# PCB_1d.net
KiCad netlist of a schematic drawn in EAGLE
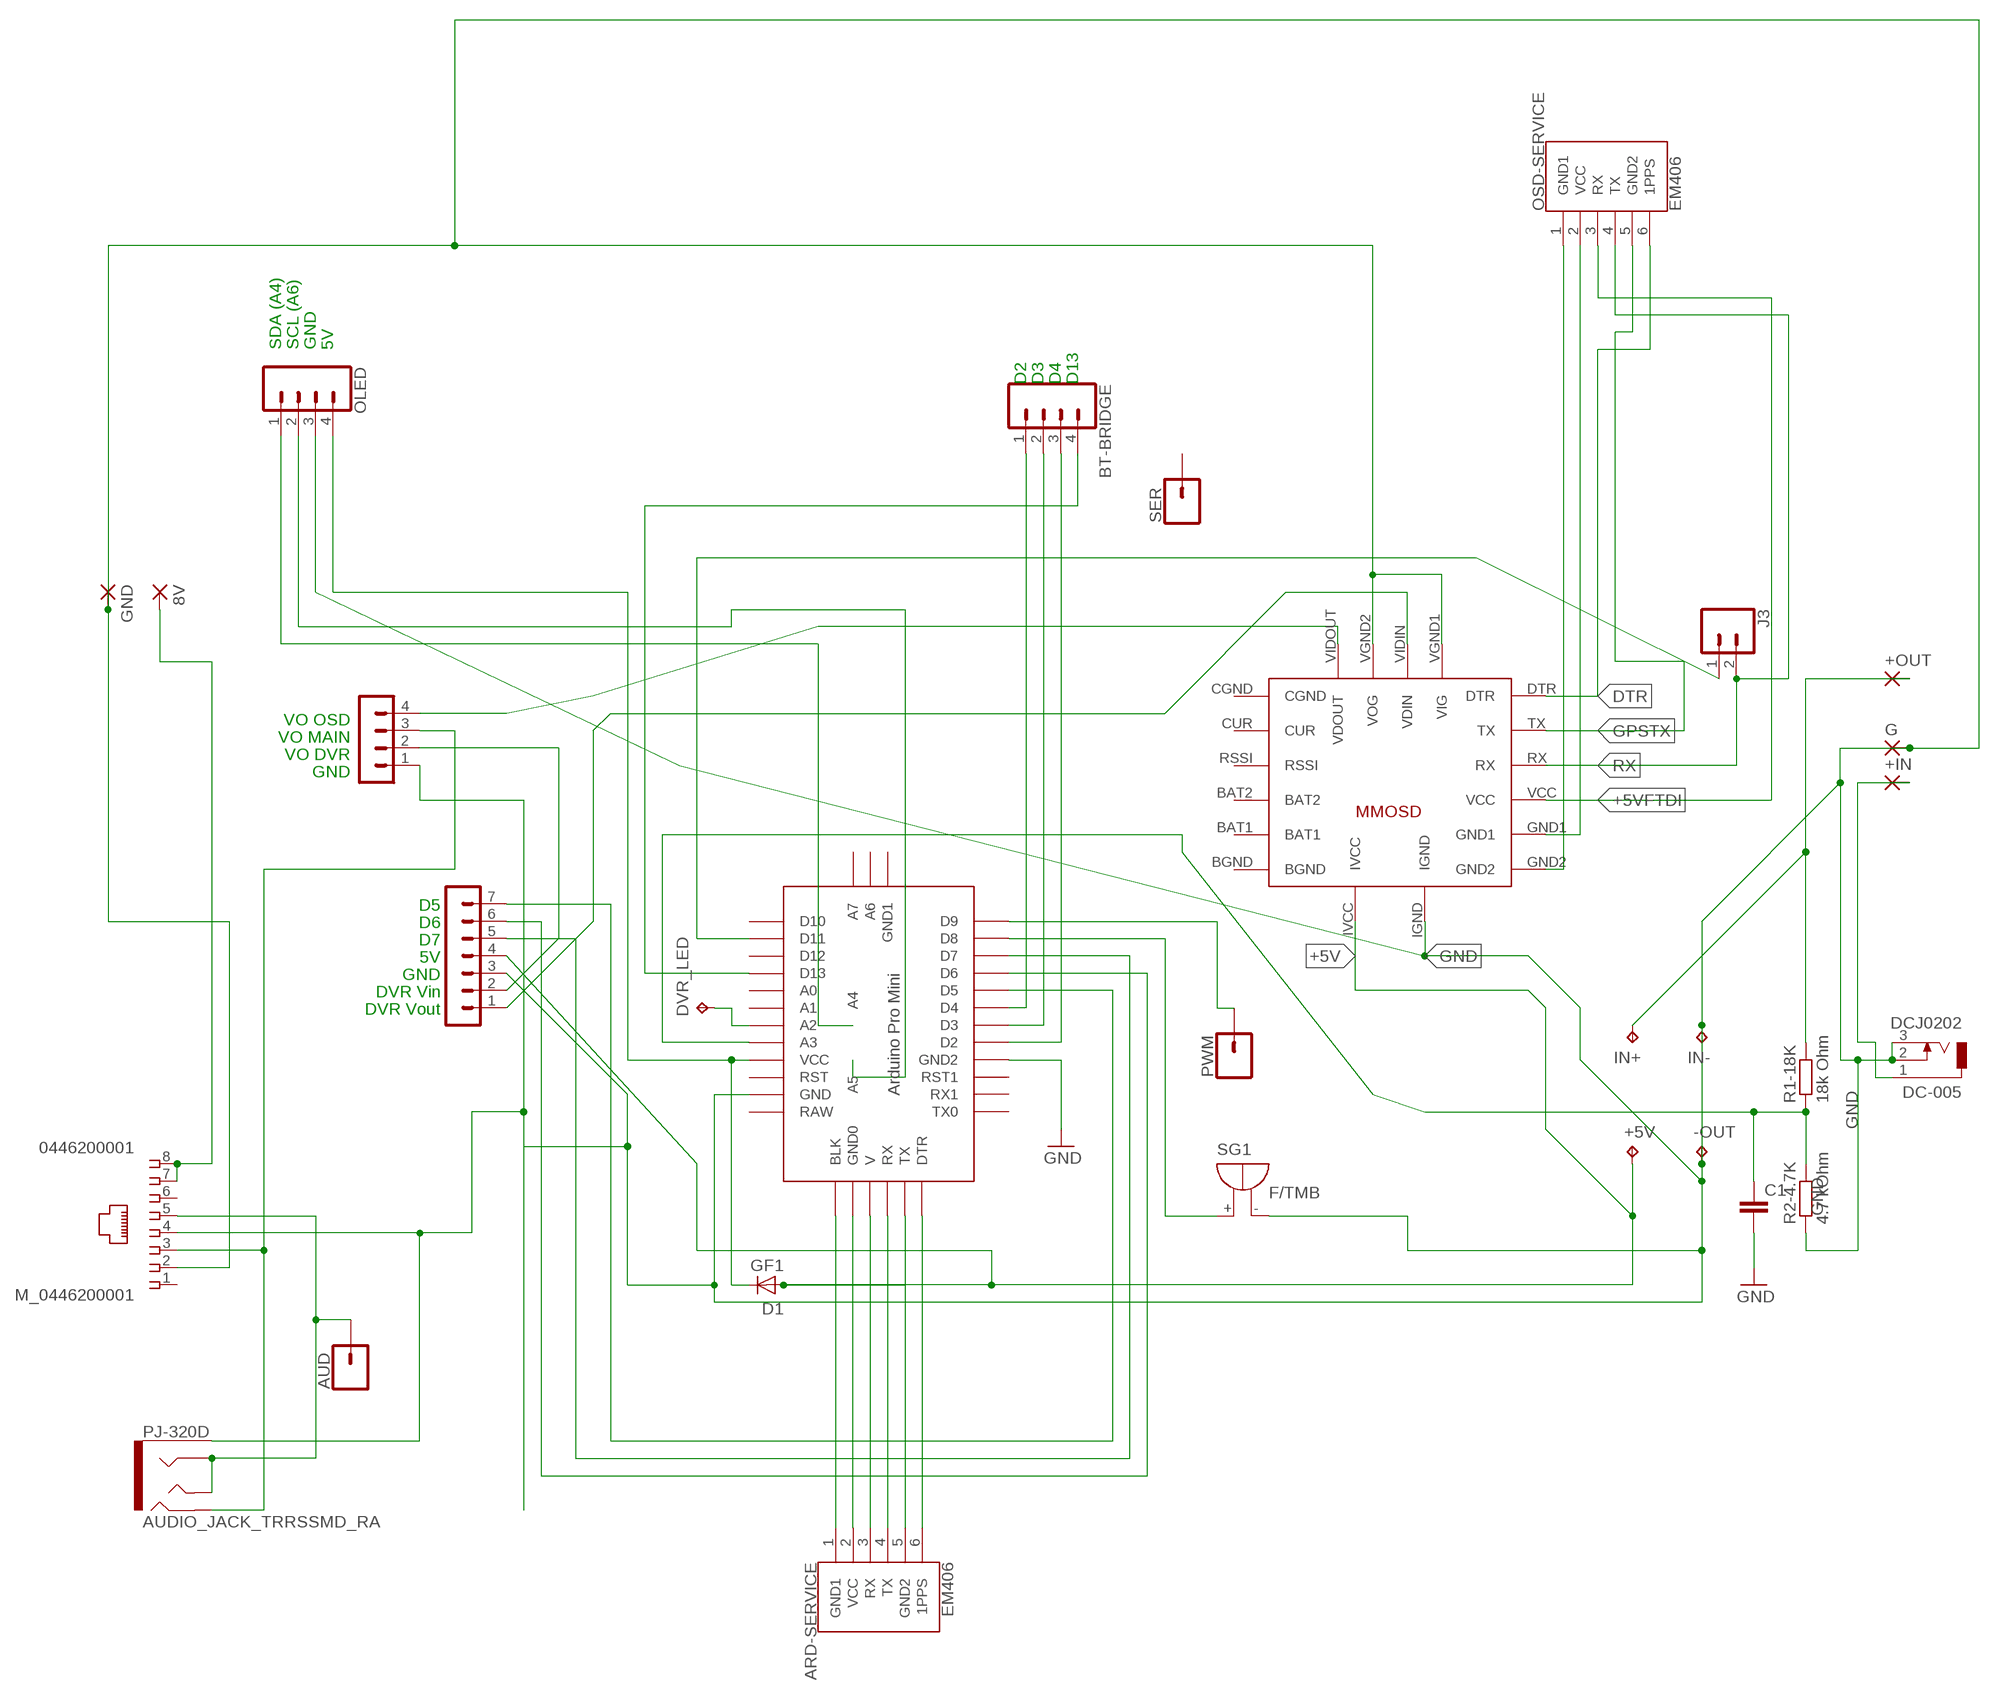
[diagram p0: schematic, sheet 1]

(export (version "E")
  (design (tool "Eeschema 10.0.6"))
  (components
    (comp (ref "+5V")
      (value "TPTP20SQ")
      (footprint "eagle-import:TP20SQ")
      (libsource (lib "eagle-import") (part "TPTP20SQ"))
    )
    (comp (ref "+IN")
      (value "2,54/1,1")
      (footprint "eagle-import:2,54_1,1")
      (libsource (lib "eagle-import") (part "2,54/1,1"))
    )
    (comp (ref "+OUT")
      (value "2,54/1,1")
      (footprint "eagle-import:2,54_1,1")
      (libsource (lib "eagle-import") (part "2,54/1,1"))
    )
    (comp (ref "-OUT")
      (value "TPTP20SQ")
      (footprint "eagle-import:TP20SQ")
      (libsource (lib "eagle-import") (part "TPTP20SQ"))
    )
    (comp (ref "8V")
      (value "2,54/1,1")
      (footprint "eagle-import:2,54_1,1")
      (libsource (lib "eagle-import") (part "2,54/1,1"))
    )
    (comp (ref "ARD-SERVICE")
      (value "EM406")
      (footprint "eagle-import:1X06-1MM")
      (libsource (lib "eagle-import") (part "EM406"))
    )
    (comp (ref "AUD")
      (value "CONN_01")
      (footprint "eagle-import:1X01")
      (libsource (lib "eagle-import") (part "CONN_01"))
    )
    (comp (ref "BT-BRIDGE")
      (value "CONN_04")
      (footprint "eagle-import:1X04")
      (libsource (lib "eagle-import") (part "CONN_04"))
    )
    (comp (ref "C1")
      (value "C-EUC1206K")
      (footprint "eagle-import:C1206K")
      (libsource (lib "eagle-import") (part "C-EUC1206K"))
    )
    (comp (ref "D1")
      (value "GF1")
      (footprint "eagle-import:SMA-DO214AC")
      (libsource (lib "eagle-import") (part "GF1"))
    )
    (comp (ref "DC-005")
      (value "DCJ0202")
      (footprint "eagle-import:DCJ0202")
      (libsource (lib "eagle-import") (part "DCJ0202"))
    )
    (comp (ref "DVR_LED")
      (value "TPTP20SQ")
      (footprint "eagle-import:TP20SQ")
      (libsource (lib "eagle-import") (part "TPTP20SQ"))
    )
    (comp (ref "G")
      (value "2,54/1,1")
      (footprint "eagle-import:2,54_1,1")
      (libsource (lib "eagle-import") (part "2,54/1,1"))
    )
    (comp (ref "GND")
      (value "2,54/1,1")
      (footprint "eagle-import:2,54_1,1")
      (libsource (lib "eagle-import") (part "2,54/1,1"))
    )
    (comp (ref "IN+")
      (value "TPTP20SQ")
      (footprint "eagle-import:TP20SQ")
      (libsource (lib "eagle-import") (part "TPTP20SQ"))
    )
    (comp (ref "IN-")
      (value "TPTP20SQ")
      (footprint "eagle-import:TP20SQ")
      (libsource (lib "eagle-import") (part "TPTP20SQ"))
    )
    (comp (ref "J3")
      (value "CONN_02")
      (footprint "eagle-import:1X02")
      (libsource (lib "eagle-import") (part "CONN_02"))
    )
    (comp (ref "MINIMOSD")
      (value "MICROMINIMOSDPWR")
      (footprint "eagle-import:MMOSDNVDVID")
      (libsource (lib "eagle-import") (part "MICROMINIMOSDPWR"))
    )
    (comp (ref "MODULE-IO")
      (value "MA07-1")
      (footprint "eagle-import:MA07-1")
      (libsource (lib "eagle-import") (part "MA07-1"))
    )
    (comp (ref "M_0446200001")
      (value "0446200001")
      (footprint "eagle-import:0446200001")
      (fields (field (name "MF") "MOLEX"))
      (libsource (lib "eagle-import") (part "0446200001"))
    )
    (comp (ref "OLED")
      (value "CONN_04")
      (footprint "eagle-import:1X04")
      (libsource (lib "eagle-import") (part "CONN_04"))
    )
    (comp (ref "OSD-SERVICE")
      (value "EM406")
      (footprint "eagle-import:1X06-1MM")
      (libsource (lib "eagle-import") (part "EM406"))
    )
    (comp (ref "PJ-320D")
      (value "AUDIO_JACK_TRRSSMD_RA")
      (footprint "eagle-import:AUDIO_JACK_3.5MM_TRRS_SMD_RA")
      (libsource (lib "eagle-import") (part "AUDIO_JACK_TRRSSMD_RA"))
    )
    (comp (ref "PWM")
      (value "CONN_01")
      (footprint "eagle-import:1X01")
      (libsource (lib "eagle-import") (part "CONN_01"))
    )
    (comp (ref "R1-18K")
      (value "18k Ohm")
      (footprint "eagle-import:M1206")
      (libsource (lib "eagle-import") (part "R-EU_M1206"))
    )
    (comp (ref "R2-4.7K")
      (value "4.7 kOhm")
      (footprint "eagle-import:M1206")
      (libsource (lib "eagle-import") (part "R-EU_M1206"))
    )
    (comp (ref "SER")
      (value "CONN_01")
      (footprint "eagle-import:1X01")
      (libsource (lib "eagle-import") (part "CONN_01"))
    )
    (comp (ref "SG1")
      (value "F/TMB")
      (footprint "eagle-import:F_TMB")
      (libsource (lib "eagle-import") (part "F/TMB"))
    )
    (comp (ref "U$1")
      (value "ABK-PRO-MINI")
      (footprint "eagle-import:ABK-PRO-MINI")
      (libsource (lib "eagle-import") (part "ABK-PRO-MINI"))
    )
    (comp (ref "V-IO")
      (value "MA04-1")
      (footprint "eagle-import:MA04-1")
      (libsource (lib "eagle-import") (part "MA04-1"))
    )
  )
  (nets
    (net (code "1") (name "+5V") (class "Default")
      (node (ref "+5V") (pin "TP") (pinfunction "TP_TP") (pintype "input"))
      (node (ref "D1") (pin "A") (pinfunction "A_A") (pintype "passive"))
      (node (ref "MINIMOSD") (pin "IVCC") (pinfunction "IVCC_IVCC") (pintype "power_in"))
      (node (ref "MODULE-IO") (pin "4") (pinfunction "4_4") (pintype "passive"))
    )
    (net (code "2") (name "+5VFTDI") (class "Default")
      (node (ref "MINIMOSD") (pin "VCC") (pinfunction "VCC_VCC") (pintype "power_in"))
      (node (ref "OSD-SERVICE") (pin "3") (pinfunction "RX_3") (pintype "bidirectional"))
    )
    (net (code "3") (name "/BAT1") (class "Default")
      (node (ref "MINIMOSD") (pin "BAT1") (pinfunction "BAT1_BAT1") (pintype "power_in"))
    )
    (net (code "4") (name "/BAT2") (class "Default")
      (node (ref "MINIMOSD") (pin "BAT2") (pinfunction "BAT2_BAT2") (pintype "power_in"))
    )
    (net (code "5") (name "/BGND") (class "Default")
      (node (ref "MINIMOSD") (pin "BGND") (pinfunction "BGND_BGND") (pintype "power_in"))
    )
    (net (code "6") (name "/CGND") (class "Default")
      (node (ref "MINIMOSD") (pin "CGND") (pinfunction "CGND_CGND") (pintype "power_in"))
    )
    (net (code "7") (name "DTR") (class "Default")
      (node (ref "MINIMOSD") (pin "DTR") (pinfunction "DTR_DTR") (pintype "bidirectional"))
      (node (ref "OSD-SERVICE") (pin "6") (pinfunction "1PPS_6") (pintype "bidirectional"))
    )
    (net (code "8") (name "GND") (class "Default")
      (node (ref "-OUT") (pin "TP") (pinfunction "TP_TP") (pintype "input"))
      (node (ref "C1") (pin "2") (pinfunction "2_2") (pintype "passive"))
      (node (ref "DC-005") (pin "2") (pinfunction "2_2") (pintype "passive"))
      (node (ref "DC-005") (pin "3") (pinfunction "3_3") (pintype "passive"))
      (node (ref "G") (pin "1") (pinfunction "P_1") (pintype "passive"))
      (node (ref "GND") (pin "1") (pinfunction "P_1") (pintype "passive"))
      (node (ref "IN-") (pin "TP") (pinfunction "TP_TP") (pintype "input"))
      (node (ref "MINIMOSD") (pin "IGND") (pinfunction "IGND_IGND") (pintype "power_in"))
      (node (ref "MINIMOSD") (pin "VGND1") (pinfunction "VIG_VGND1") (pintype "input"))
      (node (ref "MINIMOSD") (pin "VGND2") (pinfunction "VOG_VGND2") (pintype "output"))
      (node (ref "MODULE-IO") (pin "3") (pinfunction "3_3") (pintype "passive"))
      (node (ref "M_0446200001") (pin "2") (pinfunction "2_2") (pintype "passive"))
      (node (ref "M_0446200001") (pin "4") (pinfunction "4_4") (pintype "passive"))
      (node (ref "OLED") (pin "3") (pinfunction "3_3") (pintype "passive"))
      (node (ref "PJ-320D") (pin "EARTH") (pinfunction "EARTH_EARTH") (pintype "bidirectional"))
      (node (ref "R2-4.7K") (pin "1") (pinfunction "1_1") (pintype "passive"))
      (node (ref "SG1") (pin "-") (pinfunction "-_-") (pintype "passive"))
      (node (ref "U$1") (pin "GND") (pinfunction "GND_GND") (pintype "bidirectional"))
      (node (ref "U$1") (pin "GND1") (pinfunction "GND2_GND1") (pintype "bidirectional"))
      (node (ref "V-IO") (pin "1") (pinfunction "1_1") (pintype "passive"))
    )
    (net (code "9") (name "GPSTX") (class "Default")
      (node (ref "MINIMOSD") (pin "TX") (pinfunction "TX_TX") (pintype "output"))
      (node (ref "OSD-SERVICE") (pin "5") (pinfunction "GND2_5") (pintype "bidirectional"))
    )
    (net (code "10") (name "Net-(+IN-P)") (class "Default")
      (node (ref "+IN") (pin "1") (pinfunction "P_1") (pintype "passive"))
      (node (ref "DC-005") (pin "1") (pinfunction "1_1") (pintype "passive"))
    )
    (net (code "11") (name "Net-(+OUT-P)") (class "Default")
      (node (ref "+OUT") (pin "1") (pinfunction "P_1") (pintype "passive"))
      (node (ref "IN+") (pin "TP") (pinfunction "TP_TP") (pintype "input"))
      (node (ref "R1-18K") (pin "2") (pinfunction "2_2") (pintype "passive"))
    )
    (net (code "12") (name "Net-(8V-P)") (class "Default")
      (node (ref "8V") (pin "1") (pinfunction "P_1") (pintype "passive"))
      (node (ref "M_0446200001") (pin "7") (pinfunction "7_7") (pintype "passive"))
      (node (ref "M_0446200001") (pin "8") (pinfunction "8_8") (pintype "passive"))
    )
    (net (code "13") (name "Net-(ARD-SERVICE-1PPS)") (class "Default")
      (node (ref "ARD-SERVICE") (pin "6") (pinfunction "1PPS_6") (pintype "bidirectional"))
      (node (ref "U$1") (pin "DTR") (pinfunction "DTR_DTR") (pintype "bidirectional"))
    )
    (net (code "14") (name "Net-(ARD-SERVICE-GND1)") (class "Default")
      (node (ref "ARD-SERVICE") (pin "1") (pinfunction "GND1_1") (pintype "bidirectional"))
      (node (ref "U$1") (pin "BLK") (pinfunction "BLK_BLK") (pintype "bidirectional"))
    )
    (net (code "15") (name "Net-(ARD-SERVICE-GND2)") (class "Default")
      (node (ref "ARD-SERVICE") (pin "5") (pinfunction "GND2_5") (pintype "bidirectional"))
      (node (ref "U$1") (pin "TX01") (pinfunction "TX_TX01") (pintype "bidirectional"))
    )
    (net (code "16") (name "Net-(ARD-SERVICE-RX)") (class "Default")
      (node (ref "ARD-SERVICE") (pin "3") (pinfunction "RX_3") (pintype "bidirectional"))
      (node (ref "U$1") (pin "5V") (pinfunction "V_5V") (pintype "bidirectional"))
    )
    (net (code "17") (name "Net-(ARD-SERVICE-TX)") (class "Default")
      (node (ref "ARD-SERVICE") (pin "4") (pinfunction "TX_4") (pintype "bidirectional"))
      (node (ref "U$1") (pin "RX01") (pinfunction "RX_RX01") (pintype "bidirectional"))
    )
    (net (code "18") (name "Net-(ARD-SERVICE-VCC)") (class "Default")
      (node (ref "ARD-SERVICE") (pin "2") (pinfunction "VCC_2") (pintype "bidirectional"))
      (node (ref "U$1") (pin "G") (pinfunction "GND0_G") (pintype "bidirectional"))
    )
    (net (code "19") (name "Net-(AUD-Pad1)") (class "Default")
      (node (ref "AUD") (pin "1") (pinfunction "1_1") (pintype "passive"))
      (node (ref "M_0446200001") (pin "5") (pinfunction "5_5") (pintype "passive"))
      (node (ref "PJ-320D") (pin "RING1") (pinfunction "RING1_RING1") (pintype "bidirectional"))
      (node (ref "PJ-320D") (pin "TIP") (pinfunction "TIP_TIP") (pintype "bidirectional"))
    )
    (net (code "20") (name "Net-(BT-BRIDGE-Pad1)") (class "Default")
      (node (ref "BT-BRIDGE") (pin "1") (pinfunction "1_1") (pintype "passive"))
      (node (ref "U$1") (pin "D4") (pinfunction "D4_D4") (pintype "bidirectional"))
    )
    (net (code "21") (name "Net-(BT-BRIDGE-Pad2)") (class "Default")
      (node (ref "BT-BRIDGE") (pin "2") (pinfunction "2_2") (pintype "passive"))
      (node (ref "U$1") (pin "D3") (pinfunction "D3_D3") (pintype "bidirectional"))
    )
    (net (code "22") (name "Net-(BT-BRIDGE-Pad3)") (class "Default")
      (node (ref "BT-BRIDGE") (pin "3") (pinfunction "3_3") (pintype "passive"))
      (node (ref "U$1") (pin "D2") (pinfunction "D2_D2") (pintype "bidirectional"))
    )
    (net (code "23") (name "Net-(BT-BRIDGE-Pad4)") (class "Default")
      (node (ref "BT-BRIDGE") (pin "4") (pinfunction "4_4") (pintype "passive"))
      (node (ref "U$1") (pin "D13") (pinfunction "D13_D13") (pintype "bidirectional"))
    )
    (net (code "24") (name "Net-(D1-C)") (class "Default")
      (node (ref "D1") (pin "K") (pinfunction "C_K") (pintype "passive"))
      (node (ref "OLED") (pin "4") (pinfunction "4_4") (pintype "passive"))
      (node (ref "U$1") (pin "VCC") (pinfunction "VCC_VCC") (pintype "bidirectional"))
    )
    (net (code "25") (name "Net-(J3-Pad1)") (class "Default")
      (node (ref "J3") (pin "1") (pinfunction "1_1") (pintype "passive"))
      (node (ref "U$1") (pin "D11") (pinfunction "D11_D11") (pintype "bidirectional"))
    )
    (net (code "26") (name "Net-(MINIMOSD-VDIN)") (class "Default")
      (node (ref "MINIMOSD") (pin "VIDIN") (pinfunction "VDIN_VIDIN") (pintype "input"))
      (node (ref "MODULE-IO") (pin "1") (pinfunction "1_1") (pintype "passive"))
    )
    (net (code "27") (name "Net-(MINIMOSD-VDOUT)") (class "Default")
      (node (ref "MINIMOSD") (pin "VIDOUT") (pinfunction "VDOUT_VIDOUT") (pintype "output"))
      (node (ref "V-IO") (pin "4") (pinfunction "4_4") (pintype "passive"))
    )
    (net (code "28") (name "Net-(MODULE-IO-Pad2)") (class "Default")
      (node (ref "MODULE-IO") (pin "2") (pinfunction "2_2") (pintype "passive"))
      (node (ref "V-IO") (pin "2") (pinfunction "2_2") (pintype "passive"))
    )
    (net (code "29") (name "Net-(MODULE-IO-Pad5)") (class "Default")
      (node (ref "MODULE-IO") (pin "5") (pinfunction "5_5") (pintype "passive"))
      (node (ref "U$1") (pin "D7") (pinfunction "D7_D7") (pintype "bidirectional"))
    )
    (net (code "30") (name "Net-(MODULE-IO-Pad6)") (class "Default")
      (node (ref "MODULE-IO") (pin "6") (pinfunction "6_6") (pintype "passive"))
      (node (ref "U$1") (pin "D6") (pinfunction "D6_D6") (pintype "bidirectional"))
    )
    (net (code "31") (name "Net-(MODULE-IO-Pad7)") (class "Default")
      (node (ref "MODULE-IO") (pin "7") (pinfunction "7_7") (pintype "passive"))
      (node (ref "U$1") (pin "D5") (pinfunction "D5_D5") (pintype "bidirectional"))
    )
    (net (code "32") (name "Net-(M_0446200001-Pad3)") (class "Default")
      (node (ref "M_0446200001") (pin "3") (pinfunction "3_3") (pintype "passive"))
      (node (ref "PJ-320D") (pin "RING2") (pinfunction "RING2_RING2") (pintype "bidirectional"))
      (node (ref "V-IO") (pin "3") (pinfunction "3_3") (pintype "passive"))
    )
    (net (code "33") (name "Net-(OLED-Pad1)") (class "Default")
      (node (ref "OLED") (pin "1") (pinfunction "1_1") (pintype "passive"))
      (node (ref "U$1") (pin "A4") (pinfunction "A4_A4") (pintype "bidirectional"))
    )
    (net (code "34") (name "Net-(OLED-Pad2)") (class "Default")
      (node (ref "OLED") (pin "2") (pinfunction "2_2") (pintype "passive"))
      (node (ref "U$1") (pin "A5") (pinfunction "A5_A5") (pintype "bidirectional"))
    )
    (net (code "35") (name "Net-(OSD-SERVICE-GND1)") (class "Default")
      (node (ref "MINIMOSD") (pin "GND2") (pinfunction "GND2_GND2") (pintype "power_in"))
      (node (ref "OSD-SERVICE") (pin "1") (pinfunction "GND1_1") (pintype "bidirectional"))
    )
    (net (code "36") (name "Net-(OSD-SERVICE-VCC)") (class "Default")
      (node (ref "MINIMOSD") (pin "GND1") (pinfunction "GND1_GND1") (pintype "power_in"))
      (node (ref "OSD-SERVICE") (pin "2") (pinfunction "VCC_2") (pintype "bidirectional"))
    )
    (net (code "37") (name "Net-(PWM-Pad1)") (class "Default")
      (node (ref "PWM") (pin "1") (pinfunction "1_1") (pintype "passive"))
      (node (ref "U$1") (pin "D9") (pinfunction "D9_D9") (pintype "bidirectional"))
    )
    (net (code "38") (name "Net-(SG1-Pad+)") (class "Default")
      (node (ref "SG1") (pin "+") (pinfunction "+_+") (pintype "passive"))
      (node (ref "U$1") (pin "D8") (pinfunction "D8_D8") (pintype "bidirectional"))
    )
    (net (code "39") (name "Net-(U$1-A2)") (class "Default")
      (node (ref "DVR_LED") (pin "TP") (pinfunction "TP_TP") (pintype "input"))
      (node (ref "U$1") (pin "A1") (pinfunction "A2_A1") (pintype "bidirectional"))
    )
    (net (code "40") (name "Net-(U$1-A3)") (class "Default")
      (node (ref "C1") (pin "1") (pinfunction "1_1") (pintype "passive"))
      (node (ref "R1-18K") (pin "1") (pinfunction "1_1") (pintype "passive"))
      (node (ref "R2-4.7K") (pin "2") (pinfunction "2_2") (pintype "passive"))
      (node (ref "U$1") (pin "A0") (pinfunction "A3_A0") (pintype "bidirectional"))
    )
    (net (code "41") (name "RX") (class "Default")
      (node (ref "J3") (pin "2") (pinfunction "2_2") (pintype "passive"))
      (node (ref "MINIMOSD") (pin "RX") (pinfunction "RX_RX") (pintype "input"))
      (node (ref "OSD-SERVICE") (pin "4") (pinfunction "TX_4") (pintype "bidirectional"))
    )
    (net (code "42") (name "unconnected-(MINIMOSD-PadCUR)") (class "Default")
      (node (ref "MINIMOSD") (pin "CUR") (pinfunction "CUR_CUR") (pintype "bidirectional"))
    )
    (net (code "43") (name "unconnected-(MINIMOSD-PadRSSI)") (class "Default")
      (node (ref "MINIMOSD") (pin "RSSI") (pinfunction "RSSI_RSSI") (pintype "bidirectional"))
    )
    (net (code "44") (name "unconnected-(M_0446200001-Pad1)") (class "Default")
      (node (ref "M_0446200001") (pin "1") (pinfunction "1_1") (pintype "passive"))
    )
    (net (code "45") (name "unconnected-(M_0446200001-Pad6)") (class "Default")
      (node (ref "M_0446200001") (pin "6") (pinfunction "6_6") (pintype "passive"))
    )
    (net (code "46") (name "unconnected-(SER-Pad1)") (class "Default")
      (node (ref "SER") (pin "1") (pinfunction "1_1") (pintype "passive"))
    )
    (net (code "47") (name "unconnected-(U$1-A0-PadA3)") (class "Default")
      (node (ref "U$1") (pin "A3") (pinfunction "A0_A3") (pintype "bidirectional"))
    )
    (net (code "48") (name "unconnected-(U$1-A1-PadA2)") (class "Default")
      (node (ref "U$1") (pin "A2") (pinfunction "A1_A2") (pintype "bidirectional"))
    )
    (net (code "49") (name "unconnected-(U$1-GND1-PadGND4)") (class "Default")
      (node (ref "U$1") (pin "GND4") (pinfunction "GND1_GND4") (pintype "bidirectional"))
    )
    (net (code "50") (name "unconnected-(U$1-PadA6)") (class "Default")
      (node (ref "U$1") (pin "A6") (pinfunction "A6_A6") (pintype "bidirectional"))
    )
    (net (code "51") (name "unconnected-(U$1-PadA7)") (class "Default")
      (node (ref "U$1") (pin "A7") (pinfunction "A7_A7") (pintype "bidirectional"))
    )
    (net (code "52") (name "unconnected-(U$1-PadD10)") (class "Default")
      (node (ref "U$1") (pin "D10") (pinfunction "D10_D10") (pintype "bidirectional"))
    )
    (net (code "53") (name "unconnected-(U$1-PadD12)") (class "Default")
      (node (ref "U$1") (pin "D12") (pinfunction "D12_D12") (pintype "bidirectional"))
    )
    (net (code "54") (name "unconnected-(U$1-PadRAW)") (class "Default")
      (node (ref "U$1") (pin "RAW") (pinfunction "RAW_RAW") (pintype "bidirectional"))
    )
    (net (code "55") (name "unconnected-(U$1-PadRST)") (class "Default")
      (node (ref "U$1") (pin "RST") (pinfunction "RST_RST") (pintype "bidirectional"))
    )
    (net (code "56") (name "unconnected-(U$1-PadRST1)") (class "Default")
      (node (ref "U$1") (pin "RST1") (pinfunction "RST1_RST1") (pintype "bidirectional"))
    )
    (net (code "57") (name "unconnected-(U$1-PadRX1)") (class "Default")
      (node (ref "U$1") (pin "RX1") (pinfunction "RX1_RX1") (pintype "bidirectional"))
    )
    (net (code "58") (name "unconnected-(U$1-PadTX0)") (class "Default")
      (node (ref "U$1") (pin "TX0") (pinfunction "TX0_TX0") (pintype "bidirectional"))
    )
  )
)
